# PCB_KIT_89S52_OBIT.net
KiCad netlist of a schematic drawn in Altium Designer
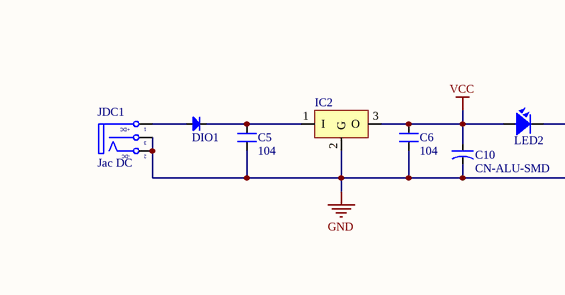
[diagram p0: PCB_KIT_89S52_OBIT.SchDoc, top left]
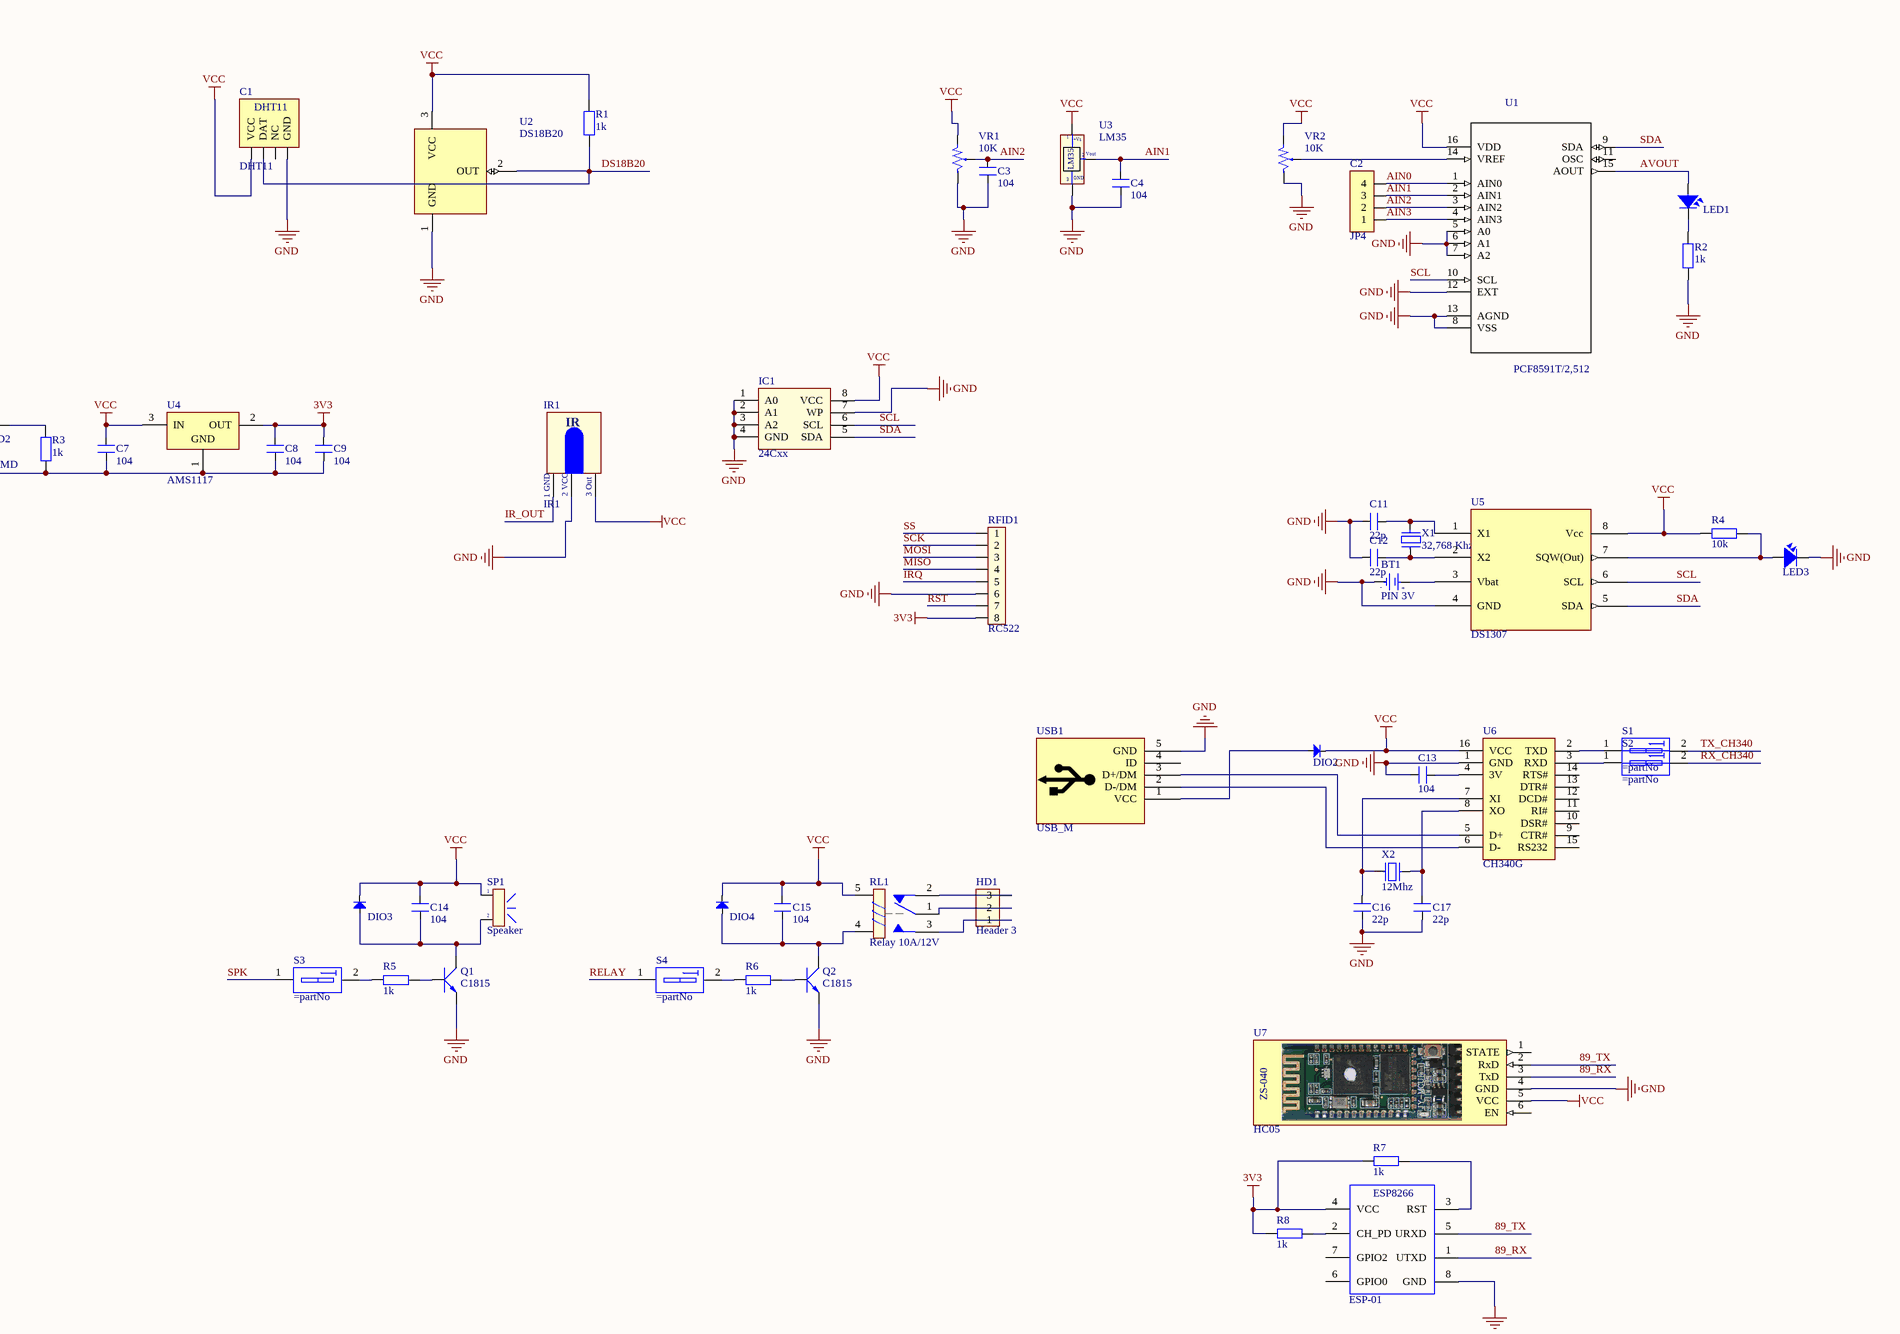
[diagram p1: PCB_KIT_89S52_OBIT.SchDoc, top right]
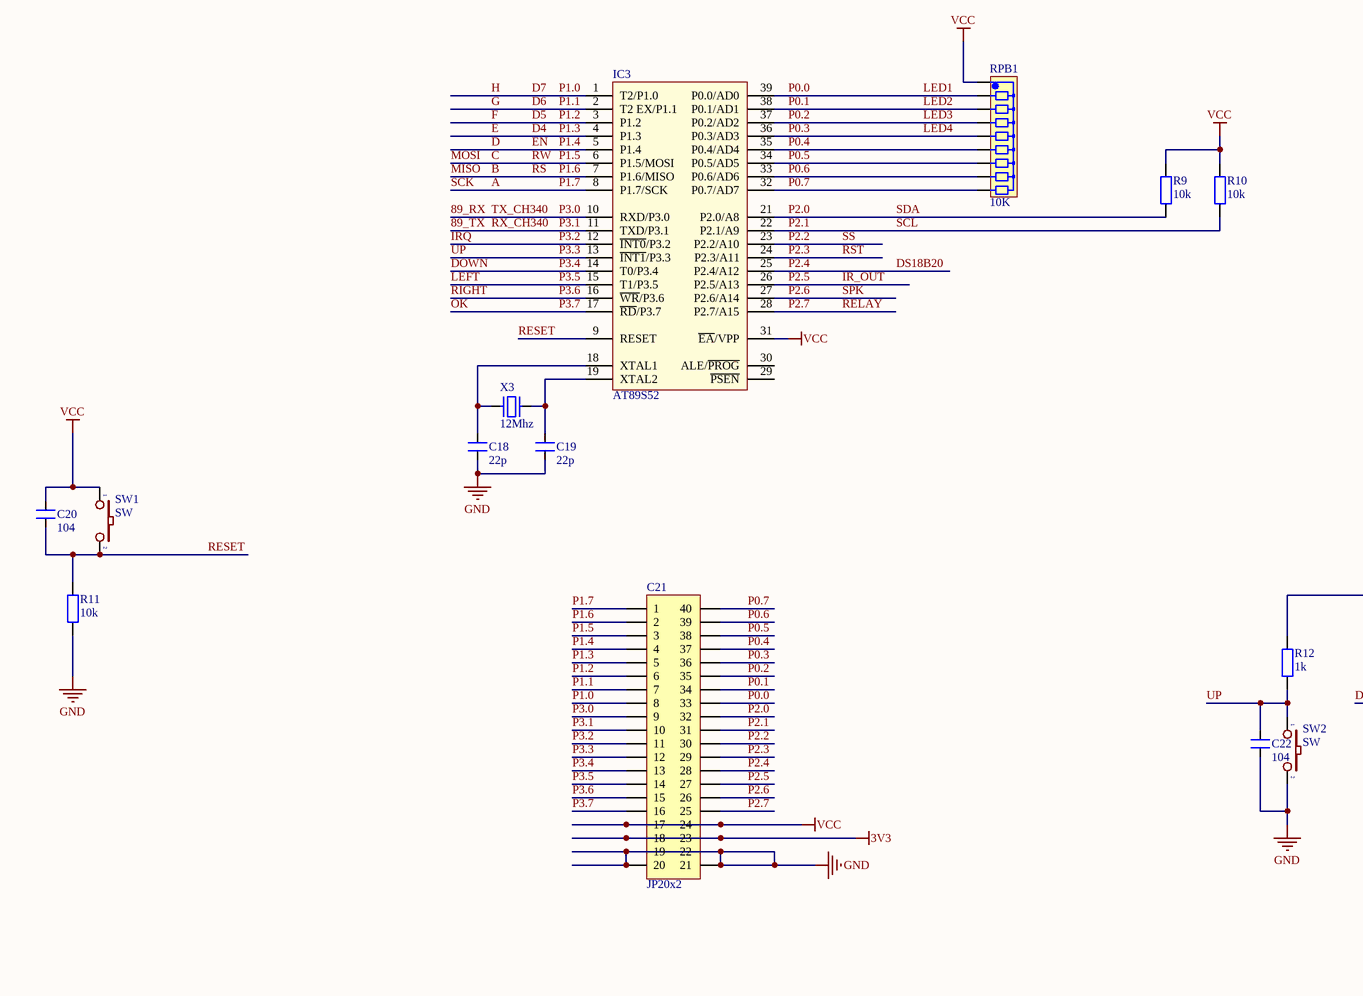
[diagram p2: PCB_KIT_89S52_OBIT.SchDoc, bottom left]
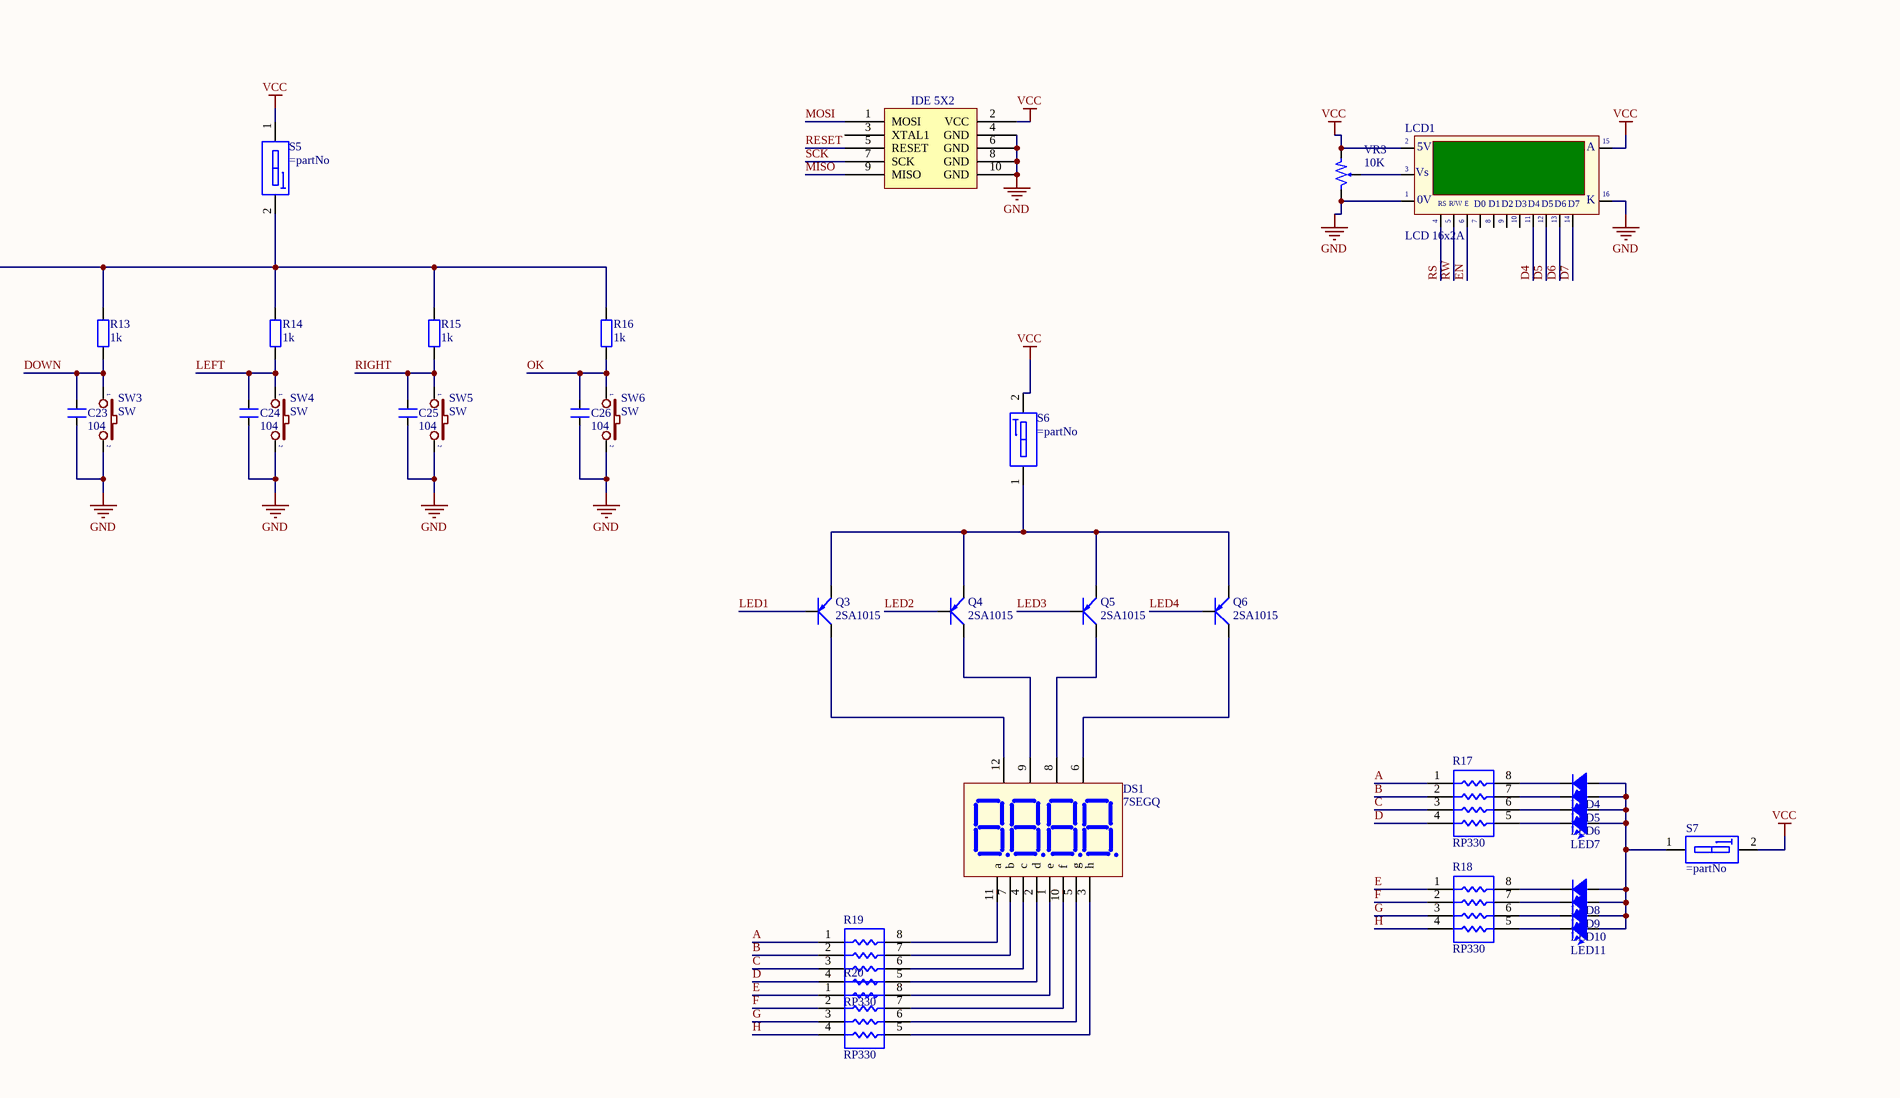
[diagram p3: PCB_KIT_89S52_OBIT.SchDoc, bottom right]

(export (version "E")
  (design (tool "Eeschema 10.0.6"))
  (components
    (comp (ref "BT1")
      (value "PIN 3V")
      (footprint "PIN CR1220-SMD")
      (description "Battery 3VDC")
      (libsource (lib "Tesla_Thinh") (part "PIN 3V"))
    )
    (comp (ref "C1")
      (value "DHT11")
      (footprint "DHT11")
      (fields
        (field (name "MANUFACTURER") "Würth Elektronik eiSos GmbH")
        (field (name "PARTNO") "613004143121")
        (field (name "CREATED BY") "Karrer Zheng")
      )
      (libsource (lib "Tesla_Thinh") (part "DHT11"))
    )
    (comp (ref "C2")
      (value "JP4")
      (footprint "JP4-C1T")
      (description "WR-PHD 2.54 mm Angled Socket Header")
      (fields
        (field (name "MANUFACTURER") "Würth Elektronik eiSos GmbH")
        (field (name "PARTNO") "613004143121")
        (field (name "CREATED BY") "Karrer Zheng")
      )
      (libsource (lib "Tesla_Thinh") (part "JP4"))
    )
    (comp (ref "C3")
      (value "104")
      (footprint "SM-0805")
      (description "Cap SMD")
      (libsource (lib "Tesla_Thinh") (part "CM"))
    )
    (comp (ref "C4")
      (value "104")
      (footprint "SM-0805")
      (description "Cap SMD")
      (libsource (lib "Tesla_Thinh") (part "CM"))
    )
    (comp (ref "C5")
      (value "104")
      (footprint "SM-0805")
      (description "Cap SMD")
      (libsource (lib "Tesla_Thinh") (part "CM"))
    )
    (comp (ref "C6")
      (value "104")
      (footprint "SM-0805")
      (description "Cap SMD")
      (libsource (lib "Tesla_Thinh") (part "CM"))
    )
    (comp (ref "C7")
      (value "104")
      (footprint "SM-0805")
      (description "Cap SMD")
      (libsource (lib "Tesla_Thinh") (part "CM"))
    )
    (comp (ref "C8")
      (value "104")
      (footprint "SM-0805")
      (description "Cap SMD")
      (libsource (lib "Tesla_Thinh") (part "CM"))
    )
    (comp (ref "C9")
      (value "104")
      (footprint "SM-0805")
      (description "Cap SMD")
      (libsource (lib "Tesla_Thinh") (part "CM"))
    )
    (comp (ref "C10")
      (value "CN-ALU-SMD")
      (footprint "CAP-ALU-SMD-5.5x5.5")
      (description "Polarized Capacitor (Axial)")
      (fields (field (name "PUBLISHER") "Altium Limited"))
      (libsource (lib "Tesla_Thinh") (part "CN-ALU-SMD"))
    )
    (comp (ref "C11")
      (value "22p")
      (footprint "SM-0805")
      (description "Cap SMD")
      (libsource (lib "Tesla_Thinh") (part "CM"))
    )
    (comp (ref "C12")
      (value "22p")
      (footprint "SM-0805")
      (description "Cap SMD")
      (libsource (lib "Tesla_Thinh") (part "CM"))
    )
    (comp (ref "C13")
      (value "104")
      (footprint "SM-0805")
      (description "Cap SMD")
      (libsource (lib "Tesla_Thinh") (part "CM"))
    )
    (comp (ref "C14")
      (value "104")
      (footprint "SM-0805")
      (description "Cap SMD")
      (libsource (lib "Tesla_Thinh") (part "CM"))
    )
    (comp (ref "C15")
      (value "104")
      (footprint "SM-0805")
      (description "Cap SMD")
      (libsource (lib "Tesla_Thinh") (part "CM"))
    )
    (comp (ref "C16")
      (value "22p")
      (footprint "SM-0805")
      (description "Cap SMD")
      (libsource (lib "Tesla_Thinh") (part "CM"))
    )
    (comp (ref "C17")
      (value "22p")
      (footprint "SM-0805")
      (description "Cap SMD")
      (libsource (lib "Tesla_Thinh") (part "CM"))
    )
    (comp (ref "C18")
      (value "22p")
      (footprint "SM-0805")
      (description "Cap SMD")
      (libsource (lib "Tesla_Thinh") (part "CM"))
    )
    (comp (ref "C19")
      (value "22p")
      (footprint "SM-0805")
      (description "Cap SMD")
      (libsource (lib "Tesla_Thinh") (part "CM"))
    )
    (comp (ref "C20")
      (value "104")
      (footprint "SM-0805")
      (description "Cap SMD")
      (libsource (lib "Tesla_Thinh") (part "CM"))
    )
    (comp (ref "C21")
      (value "JP20x2")
      (footprint "JP20-C2T")
      (description "WR-PHD 2.54 mm Dual Socket Header")
      (fields
        (field (name "MANUFACTURER") "Würth Elektronik eiSos GmbH")
        (field (name "PARTNO") "61304021821")
        (field (name "CREATED BY") "Karrer Zheng")
      )
      (libsource (lib "Tesla_Thinh") (part "JP20x2"))
    )
    (comp (ref "C22")
      (value "104")
      (footprint "SM-0805")
      (description "Cap SMD")
      (libsource (lib "Tesla_Thinh") (part "CM"))
    )
    (comp (ref "C23")
      (value "104")
      (footprint "SM-0805")
      (description "Cap SMD")
      (libsource (lib "Tesla_Thinh") (part "CM"))
    )
    (comp (ref "C24")
      (value "104")
      (footprint "SM-0805")
      (description "Cap SMD")
      (libsource (lib "Tesla_Thinh") (part "CM"))
    )
    (comp (ref "C25")
      (value "104")
      (footprint "SM-0805")
      (description "Cap SMD")
      (libsource (lib "Tesla_Thinh") (part "CM"))
    )
    (comp (ref "C26")
      (value "104")
      (footprint "SM-0805")
      (description "Cap SMD")
      (libsource (lib "Tesla_Thinh") (part "CM"))
    )
    (comp (ref "DIO1")
      (value "Diode SMD")
      (footprint "DIO-SMD-106")
      (description "Default Diode")
      (fields (field (name "PUBLISHER") "Altium Limited"))
      (libsource (lib "Obit_Library") (part "Diode SMD"))
    )
    (comp (ref "DIO2")
      (value "Diode SMD")
      (footprint "DIO-SMD-106")
      (description "Default Diode")
      (fields (field (name "PUBLISHER") "Altium Limited"))
      (libsource (lib "Obit_Library") (part "Diode SMD"))
    )
    (comp (ref "DIO3")
      (value "Diode SMD")
      (footprint "DIO-SMD-106")
      (description "Default Diode")
      (fields (field (name "PUBLISHER") "Altium Limited"))
      (libsource (lib "Obit_Library") (part "Diode SMD"))
    )
    (comp (ref "DIO4")
      (value "Diode SMD")
      (footprint "DIO-SMD-106")
      (description "Default Diode")
      (fields (field (name "PUBLISHER") "Altium Limited"))
      (libsource (lib "Obit_Library") (part "Diode SMD"))
    )
    (comp (ref "DS1")
      (value "7SEGQ")
      (footprint "LED7SEG-4-0.56")
      (description "Four 7 Seg Dipslay")
      (libsource (lib "Tesla_Thinh") (part "LED7SEG-4"))
    )
    (comp (ref "HD1")
      (value "Header 3")
      (footprint "HED3")
      (description "Header 3 (Green)")
      (libsource (lib "Obit_Library") (part "Hed3"))
    )
    (comp (ref "IC1")
      (value "24Cxx")
      (footprint "SO8")
      (description "Standard 2-Wire Bus Interface Serial EEPROM")
      (fields (field (name "COPYRIGHT BY") "VanDungEvn"))
      (libsource (lib "Obit_Library") (part "24Cxx"))
    )
    (comp (ref "IC2")
      (value "LM78xx")
      (footprint "TO252-123")
      (description "Positive Voltage Regulator")
      (fields (field (name "PUBLISHER") "Altium Limited"))
      (libsource (lib "Tesla_Thinh") (part "LM78xx"))
    )
    (comp (ref "IC3")
      (value "AT89S52")
      (footprint "DIP40_Socket")
      (description "AT89S52, 8k Byte Flash Memory , 40 Pin")
      (libsource (lib "Obit_Library") (part "AT89S52"))
    )
    (comp (ref "IDE_1")
      (value "IDE 5X2")
      (footprint "HDR2X5")
      (description "IDE 5X2 DUC-THANG")
      (libsource (lib "Lib_Chuan_03_08_2013") (part "ISP"))
    )
    (comp (ref "IR1")
      (value "IR1")
      (footprint "IR2")
      (description "Receiver Infraed IC")
      (libsource (lib "Tesla_Thinh") (part "IR1"))
    )
    (comp (ref "JDC1")
      (value "Jac DC")
      (footprint "DC0")
      (description "Jac DC input")
      (libsource (lib "Tesla_Thinh") (part "DCIN"))
    )
    (comp (ref "LCD1")
      (value "LCD 16x2A")
      (footprint "LCD16X2N")
      (description "LCD dipslay 16 char, 2 line")
      (libsource (lib "Tesla_Thinh") (part "LCD16x2A"))
    )
    (comp (ref "LED1")
      (value "LED")
      (footprint "LED-0805-Green")
      (libsource (lib "Tesla_Thinh") (part "LED SMD"))
    )
    (comp (ref "LED2")
      (value "LED")
      (footprint "LED-0805-Green")
      (libsource (lib "Tesla_Thinh") (part "LED SMD"))
    )
    (comp (ref "LED3")
      (value "LED")
      (footprint "LED-0805-Green")
      (libsource (lib "Tesla_Thinh") (part "LED SMD"))
    )
    (comp (ref "LED4")
      (value "LED")
      (footprint "LED-0805-Green")
      (libsource (lib "Tesla_Thinh") (part "LED SMD"))
    )
    (comp (ref "LED5")
      (value "LED")
      (footprint "LED-0805-Green")
      (libsource (lib "Tesla_Thinh") (part "LED SMD"))
    )
    (comp (ref "LED6")
      (value "LED")
      (footprint "LED-0805-Green")
      (libsource (lib "Tesla_Thinh") (part "LED SMD"))
    )
    (comp (ref "LED7")
      (value "LED")
      (footprint "LED-0805-Green")
      (libsource (lib "Tesla_Thinh") (part "LED SMD"))
    )
    (comp (ref "LED8")
      (value "LED")
      (footprint "LED-0805-Green")
      (libsource (lib "Tesla_Thinh") (part "LED SMD"))
    )
    (comp (ref "LED9")
      (value "LED")
      (footprint "LED-0805-Green")
      (libsource (lib "Tesla_Thinh") (part "LED SMD"))
    )
    (comp (ref "LED10")
      (value "LED")
      (footprint "LED-0805-Green")
      (libsource (lib "Tesla_Thinh") (part "LED SMD"))
    )
    (comp (ref "LED11")
      (value "LED")
      (footprint "LED-0805-Green")
      (libsource (lib "Tesla_Thinh") (part "LED SMD"))
    )
    (comp (ref "Q1")
      (value "C1815")
      (footprint "SOT23B")
      (description "NPN 600mW, ECB")
      (libsource (lib "Obit_Library") (part "C1815"))
    )
    (comp (ref "Q2")
      (value "C1815")
      (footprint "SOT23B")
      (description "NPN 600mW, ECB")
      (libsource (lib "Obit_Library") (part "C1815"))
    )
    (comp (ref "Q3")
      (value "2SA1015")
      (footprint "SOT23-321")
      (description "PNP 600mW, ECB")
      (libsource (lib "OBIT_TESLA") (part "2SA1015"))
    )
    (comp (ref "Q4")
      (value "2SA1015")
      (footprint "SOT23-321")
      (description "PNP 600mW, ECB")
      (libsource (lib "OBIT_TESLA") (part "2SA1015"))
    )
    (comp (ref "Q5")
      (value "2SA1015")
      (footprint "SOT23-321")
      (description "PNP 600mW, ECB")
      (libsource (lib "OBIT_TESLA") (part "2SA1015"))
    )
    (comp (ref "Q6")
      (value "2SA1015")
      (footprint "SOT23-321")
      (description "PNP 600mW, ECB")
      (libsource (lib "OBIT_TESLA") (part "2SA1015"))
    )
    (comp (ref "R1")
      (value "1k")
      (footprint "SM-RES-0805")
      (description "Resistor 1/4W")
      (libsource (lib "Tesla_Thinh") (part "R1/4W"))
    )
    (comp (ref "R2")
      (value "1k")
      (footprint "SM-RES-0805")
      (description "Resistor 1/4W")
      (libsource (lib "Tesla_Thinh") (part "R1/4W"))
    )
    (comp (ref "R3")
      (value "1k")
      (footprint "SM-RES-0805")
      (description "Resistor 1/4W")
      (libsource (lib "Tesla_Thinh") (part "R1/4W"))
    )
    (comp (ref "R4")
      (value "10k")
      (footprint "SM-RES-0805")
      (description "Resistor 1/4W")
      (libsource (lib "Tesla_Thinh") (part "R1/4W"))
    )
    (comp (ref "R5")
      (value "1k")
      (footprint "SM-RES-0805")
      (description "Resistor 1/4W")
      (libsource (lib "Tesla_Thinh") (part "R1/4W"))
    )
    (comp (ref "R6")
      (value "1k")
      (footprint "SM-RES-0805")
      (description "Resistor 1/4W")
      (libsource (lib "Tesla_Thinh") (part "R1/4W"))
    )
    (comp (ref "R7")
      (value "1k")
      (footprint "SM-RES-0805")
      (description "Resistor 1/4W")
      (libsource (lib "Tesla_Thinh") (part "R1/4W"))
    )
    (comp (ref "R8")
      (value "1k")
      (footprint "SM-RES-0805")
      (description "Resistor 1/4W")
      (libsource (lib "Tesla_Thinh") (part "R1/4W"))
    )
    (comp (ref "R9")
      (value "10k")
      (footprint "SM-RES-0805")
      (description "Resistor 1/4W")
      (libsource (lib "Tesla_Thinh") (part "R1/4W"))
    )
    (comp (ref "R10")
      (value "10k")
      (footprint "SM-RES-0805")
      (description "Resistor 1/4W")
      (libsource (lib "Tesla_Thinh") (part "R1/4W"))
    )
    (comp (ref "R11")
      (value "10k")
      (footprint "SM-RES-0805")
      (description "Resistor 1/4W")
      (libsource (lib "Tesla_Thinh") (part "R1/4W"))
    )
    (comp (ref "R12")
      (value "1k")
      (footprint "SM-RES-0805")
      (description "Resistor 1/4W")
      (libsource (lib "Tesla_Thinh") (part "R1/4W"))
    )
    (comp (ref "R13")
      (value "1k")
      (footprint "SM-RES-0805")
      (description "Resistor 1/4W")
      (libsource (lib "Tesla_Thinh") (part "R1/4W"))
    )
    (comp (ref "R14")
      (value "1k")
      (footprint "SM-RES-0805")
      (description "Resistor 1/4W")
      (libsource (lib "Tesla_Thinh") (part "R1/4W"))
    )
    (comp (ref "R15")
      (value "1k")
      (footprint "SM-RES-0805")
      (description "Resistor 1/4W")
      (libsource (lib "Tesla_Thinh") (part "R1/4W"))
    )
    (comp (ref "R16")
      (value "1k")
      (footprint "SM-RES-0805")
      (description "Resistor 1/4W")
      (libsource (lib "Tesla_Thinh") (part "R1/4W"))
    )
    (comp (ref "R17")
      (value "RP330")
      (footprint "RESCAXS50P160X320X70-8N")
      (libsource (lib "Obit_Library") (part "ResPack"))
    )
    (comp (ref "R18")
      (value "RP330")
      (footprint "RESCAXS50P160X320X70-8N")
      (libsource (lib "Obit_Library") (part "ResPack"))
    )
    (comp (ref "R19")
      (value "RP330")
      (footprint "RESCAXS50P160X320X70-8N")
      (libsource (lib "Obit_Library") (part "ResPack"))
    )
    (comp (ref "R20")
      (value "RP330")
      (footprint "RESCAXS50P160X320X70-8N")
      (libsource (lib "Obit_Library") (part "ResPack"))
    )
    (comp (ref "RFID1")
      (value "RC522")
      (footprint "JP8")
      (description "JP8 PIN")
      (libsource (lib "Obit_Library") (part "JP8"))
    )
    (comp (ref "RL1")
      (value "Relay 10A/12V")
      (footprint "RL_SPDT_10A")
      (description "Relay SPDT,10A - 12VDC 5 Pin")
      (libsource (lib "Obit_Library") (part "Relay 1"))
    )
    (comp (ref "RPB1")
      (value "10K")
      (footprint "RN8")
      (description "Resistor 8 (Thanh)")
      (libsource (lib "Tesla_Thinh") (part "RN8"))
    )
    (comp (ref "S1")
      (value "~")
      (footprint "SW-DIP1-1")
      (description "WS-DITV 2.54 mm small compact THT flat actuator with top tape")
      (fields
        (field (name "MANUFACTURER") "Wurth Elektronik")
        (field (name "PART NO.") "418127160901")
        (field (name "CREATED BY") "Baojun Chen")
      )
      (libsource (lib "Tesla_Thinh") (part "SWDIP1"))
    )
    (comp (ref "S2")
      (value "~")
      (footprint "SW-DIP1-1")
      (description "WS-DITV 2.54 mm small compact THT flat actuator with top tape")
      (fields
        (field (name "MANUFACTURER") "Wurth Elektronik")
        (field (name "PART NO.") "418127160901")
        (field (name "CREATED BY") "Baojun Chen")
      )
      (libsource (lib "Tesla_Thinh") (part "SWDIP1"))
    )
    (comp (ref "S3")
      (value "~")
      (footprint "SW-DIP1-1")
      (description "WS-DITV 2.54 mm small compact THT flat actuator with top tape")
      (fields
        (field (name "MANUFACTURER") "Wurth Elektronik")
        (field (name "PART NO.") "418127160901")
        (field (name "CREATED BY") "Baojun Chen")
      )
      (libsource (lib "Tesla_Thinh") (part "SWDIP1"))
    )
    (comp (ref "S4")
      (value "~")
      (footprint "SW-DIP1-1")
      (description "WS-DITV 2.54 mm small compact THT flat actuator with top tape")
      (fields
        (field (name "MANUFACTURER") "Wurth Elektronik")
        (field (name "PART NO.") "418127160901")
        (field (name "CREATED BY") "Baojun Chen")
      )
      (libsource (lib "Tesla_Thinh") (part "SWDIP1"))
    )
    (comp (ref "S5")
      (value "~")
      (footprint "SW-DIP1-1")
      (description "WS-DITV 2.54 mm small compact THT flat actuator with top tape")
      (fields
        (field (name "MANUFACTURER") "Wurth Elektronik")
        (field (name "PART NO.") "418127160901")
        (field (name "CREATED BY") "Baojun Chen")
      )
      (libsource (lib "") (part "SWDIP1_1"))
    )
    (comp (ref "S6")
      (value "~")
      (footprint "SW-DIP1-1")
      (description "WS-DITV 2.54 mm small compact THT flat actuator with top tape")
      (fields
        (field (name "MANUFACTURER") "Wurth Elektronik")
        (field (name "PART NO.") "418127160901")
        (field (name "CREATED BY") "Baojun Chen")
      )
      (libsource (lib "") (part "SWDIP1_2"))
    )
    (comp (ref "S7")
      (value "~")
      (footprint "SW-DIP1-1")
      (description "WS-DITV 2.54 mm small compact THT flat actuator with top tape")
      (fields
        (field (name "MANUFACTURER") "Wurth Elektronik")
        (field (name "PART NO.") "418127160901")
        (field (name "CREATED BY") "Baojun Chen")
      )
      (libsource (lib "Tesla_Thinh") (part "SWDIP1"))
    )
    (comp (ref "SP1")
      (value "Speaker")
      (footprint "SPK")
      (description "Speaker Chip")
      (libsource (lib "Obit_Library") (part "SPK"))
    )
    (comp (ref "SW1")
      (value "SW")
      (footprint "SW1-SMD")
      (description "Switch button 2 pin")
      (libsource (lib "Tesla_Thinh") (part "SW2"))
    )
    (comp (ref "SW2")
      (value "SW")
      (footprint "SW1-SMD")
      (description "Switch button 2 pin")
      (libsource (lib "Tesla_Thinh") (part "SW2"))
    )
    (comp (ref "SW3")
      (value "SW")
      (footprint "SW1-SMD")
      (description "Switch button 2 pin")
      (libsource (lib "Tesla_Thinh") (part "SW2"))
    )
    (comp (ref "SW4")
      (value "SW")
      (footprint "SW1-SMD")
      (description "Switch button 2 pin")
      (libsource (lib "Tesla_Thinh") (part "SW2"))
    )
    (comp (ref "SW5")
      (value "SW")
      (footprint "SW1-SMD")
      (description "Switch button 2 pin")
      (libsource (lib "Tesla_Thinh") (part "SW2"))
    )
    (comp (ref "SW6")
      (value "SW")
      (footprint "SW1-SMD")
      (description "Switch button 2 pin")
      (libsource (lib "Tesla_Thinh") (part "SW2"))
    )
    (comp (ref "U1")
      (value "PCF8591T/2,512")
      (footprint "SOIC127P1032X265-16N")
      (description "PCF8591 Series 2.5 V - 6 V Bá»™ chuyá»ƒn Ä‘á»•i A / D 8-bit vÃ  D / A - SOIC - 16")
      (fields (field (name "MF") "NXP Semiconductors"))
      (libsource (lib "PCF8591T_2_512") (part "PCF8591T/2,512"))
    )
    (comp (ref "U2")
      (value "DS18B20")
      (footprint "TO-92A")
      (description "1-Wire Digital Thermometer")
      (fields (field (name "CREATOR") "Cao Van Huong"))
      (libsource (lib "Obit_Library") (part "DS18B20"))
    )
    (comp (ref "U3")
      (value "LM35")
      (footprint "TO92-123")
      (description "Teminal")
      (libsource (lib "Tesla_Thinh") (part "LM35"))
    )
    (comp (ref "U4") (value "AMS1117") (footprint "SOT 223") (libsource (lib "Obit_Library") (part "AMS117")))
    (comp (ref "U5")
      (value "DS1307")
      (footprint "SOP 8")
      (description "64 X 8 Serial Real-Time Clock")
      (libsource (lib "Obit_Library") (part "DS1307"))
    )
    (comp (ref "U6")
      (value "CH340G")
      (footprint "SO16")
      (description "High and Low Side Driver")
      (fields (field (name "PUBLISHER") "Altium Limited"))
      (libsource (lib "Obit_Library") (part "CH340G"))
    )
    (comp (ref "U7")
      (value "HC05")
      (footprint "JP6-C1T")
      (libsource (lib "Tesla_Thinh") (part "Module ZS-040 (HC05)"))
    )
    (comp (ref "U8")
      (value "ESP-01")
      (footprint "ESP8266")
      (description "ESP-12 Wi-Fi Module")
      (libsource (lib "Tesla_Thinh") (part "ESP8266-01"))
    )
    (comp (ref "USB1") (value "USB_M") (footprint "USB-M1") (libsource (lib "OBIT_TESLA") (part "USB_M")))
    (comp (ref "VR1")
      (value "10K")
      (footprint "VR1")
      (description "Var Resistor")
      (libsource (lib "Tesla_Thinh") (part "VR1"))
    )
    (comp (ref "VR2")
      (value "10K")
      (footprint "VR1")
      (description "Var Resistor")
      (libsource (lib "Tesla_Thinh") (part "VR1"))
    )
    (comp (ref "VR3")
      (value "10K")
      (footprint "VR")
      (description "Var Resistor")
      (libsource (lib "Tesla_Thinh") (part "VR1"))
    )
    (comp (ref "X1")
      (value "32,768 Khz")
      (footprint "XT32k")
      (description "Crystal 32,768kHz for timer real")
      (libsource (lib "Tesla_Thinh") (part "XT32k"))
    )
    (comp (ref "X2")
      (value "12Mhz")
      (footprint "XT2")
      (description "Crystal, 32.768 KHz, -40 to 85 degC, 3.2 x 1.5 x 0.9 mm SMD")
      (libsource (lib "Tesla_Thinh") (part "XT2"))
    )
    (comp (ref "X3")
      (value "12Mhz")
      (footprint "XT2")
      (description "Crystal, 32.768 KHz, -40 to 85 degC, 3.2 x 1.5 x 0.9 mm SMD")
      (libsource (lib "Tesla_Thinh") (part "XT2"))
    )
  )
  (nets
    (net (code "1") (name "/89_RX") (class "Default")
      (node (ref "C21") (pin "9") (pinfunction "9_9") (pintype "passive"))
      (node (ref "IC3") (pin "10") (pinfunction "RXD/P3.0_10") (pintype "passive"))
      (node (ref "S1") (pin "2") (pinfunction "2_2") (pintype "passive"))
      (node (ref "U7") (pin "3") (pinfunction "TxD_3") (pintype "power_in"))
      (node (ref "U8") (pin "1") (pinfunction "UTXD_1") (pintype "passive"))
    )
    (net (code "2") (name "/89_TX") (class "Default")
      (node (ref "C21") (pin "10") (pinfunction "10_10") (pintype "passive"))
      (node (ref "IC3") (pin "11") (pinfunction "TXD/P3.1_11") (pintype "passive"))
      (node (ref "S2") (pin "2") (pinfunction "2_2") (pintype "passive"))
      (node (ref "U7") (pin "2") (pinfunction "RxD_2") (pintype "input"))
      (node (ref "U8") (pin "5") (pinfunction "URXD_5") (pintype "passive"))
    )
    (net (code "3") (name "/A") (class "Default")
      (node (ref "C21") (pin "1") (pinfunction "1_1") (pintype "passive"))
      (node (ref "IC3") (pin "8") (pinfunction "P1.7/SCK_8") (pintype "passive"))
      (node (ref "IDE_1") (pin "7") (pinfunction "SCK_7") (pintype "passive"))
      (node (ref "R17") (pin "1") (pinfunction "1_1") (pintype "passive"))
      (node (ref "R19") (pin "1") (pinfunction "1_1") (pintype "passive"))
      (node (ref "RFID1") (pin "2") (pinfunction "2_2") (pintype "passive"))
    )
    (net (code "4") (name "/AIN0") (class "Default")
      (node (ref "C2") (pin "4") (pinfunction "4_4") (pintype "passive"))
      (node (ref "U1") (pin "1") (pinfunction "AIN0_1") (pintype "input"))
    )
    (net (code "5") (name "/AIN1") (class "Default")
      (node (ref "C2") (pin "3") (pinfunction "3_3") (pintype "passive"))
      (node (ref "C4") (pin "1") (pinfunction "1_1") (pintype "passive"))
      (node (ref "U1") (pin "2") (pinfunction "AIN1_2") (pintype "input"))
      (node (ref "U3") (pin "2") (pinfunction "Vout_2") (pintype "passive"))
    )
    (net (code "6") (name "/AIN2") (class "Default")
      (node (ref "C2") (pin "2") (pinfunction "2_2") (pintype "passive"))
      (node (ref "C3") (pin "1") (pinfunction "1_1") (pintype "passive"))
      (node (ref "U1") (pin "3") (pinfunction "AIN2_3") (pintype "input"))
      (node (ref "VR1") (pin "2") (pinfunction "2_2") (pintype "passive"))
    )
    (net (code "7") (name "/AIN3") (class "Default")
      (node (ref "C2") (pin "1") (pinfunction "1_1") (pintype "passive"))
      (node (ref "U1") (pin "4") (pinfunction "AIN3_4") (pintype "input"))
    )
    (net (code "8") (name "/AVOUT") (class "Default")
      (node (ref "LED1") (pin "1") (pinfunction "1_1") (pintype "passive"))
      (node (ref "U1") (pin "15") (pinfunction "AOUT_15") (pintype "output"))
    )
    (net (code "9") (name "/B") (class "Default")
      (node (ref "C21") (pin "2") (pinfunction "2_2") (pintype "passive"))
      (node (ref "IC3") (pin "7") (pinfunction "P1.6/MISO_7") (pintype "passive"))
      (node (ref "IDE_1") (pin "9") (pinfunction "MISO_9") (pintype "passive"))
      (node (ref "LCD1") (pin "4") (pinfunction "RS_4") (pintype "passive"))
      (node (ref "R17") (pin "2") (pinfunction "2_2") (pintype "passive"))
      (node (ref "R19") (pin "2") (pinfunction "2_2") (pintype "passive"))
      (node (ref "RFID1") (pin "4") (pinfunction "4_4") (pintype "passive"))
    )
    (net (code "10") (name "/C") (class "Default")
      (node (ref "C21") (pin "3") (pinfunction "3_3") (pintype "passive"))
      (node (ref "IC3") (pin "6") (pinfunction "P1.5/MOSI_6") (pintype "passive"))
      (node (ref "IDE_1") (pin "1") (pinfunction "MOSI_1") (pintype "passive"))
      (node (ref "LCD1") (pin "5") (pinfunction "R/~{W}_5") (pintype "passive"))
      (node (ref "R17") (pin "3") (pinfunction "3_3") (pintype "passive"))
      (node (ref "R19") (pin "3") (pinfunction "3_3") (pintype "passive"))
      (node (ref "RFID1") (pin "3") (pinfunction "3_3") (pintype "passive"))
    )
    (net (code "11") (name "/D") (class "Default")
      (node (ref "C21") (pin "4") (pinfunction "4_4") (pintype "passive"))
      (node (ref "IC3") (pin "5") (pinfunction "P1.4_5") (pintype "passive"))
      (node (ref "LCD1") (pin "6") (pinfunction "~{EN}_6") (pintype "passive"))
      (node (ref "R17") (pin "4") (pinfunction "4_4") (pintype "passive"))
      (node (ref "R19") (pin "4") (pinfunction "4_4") (pintype "passive"))
    )
    (net (code "12") (name "/D4") (class "Default")
      (node (ref "C21") (pin "5") (pinfunction "5_5") (pintype "passive"))
      (node (ref "IC3") (pin "4") (pinfunction "P1.3_4") (pintype "passive"))
      (node (ref "LCD1") (pin "11") (pinfunction "D4_11") (pintype "passive"))
      (node (ref "R18") (pin "1") (pinfunction "1_1") (pintype "passive"))
      (node (ref "R20") (pin "1") (pinfunction "1_1") (pintype "passive"))
    )
    (net (code "13") (name "/D5") (class "Default")
      (node (ref "C21") (pin "6") (pinfunction "6_6") (pintype "passive"))
      (node (ref "IC3") (pin "3") (pinfunction "P1.2_3") (pintype "passive"))
      (node (ref "LCD1") (pin "12") (pinfunction "D5_12") (pintype "passive"))
      (node (ref "R18") (pin "2") (pinfunction "2_2") (pintype "passive"))
      (node (ref "R20") (pin "2") (pinfunction "2_2") (pintype "passive"))
    )
    (net (code "14") (name "/D6") (class "Default")
      (node (ref "C21") (pin "7") (pinfunction "7_7") (pintype "passive"))
      (node (ref "IC3") (pin "2") (pinfunction "T2_EX/P1.1_2") (pintype "passive"))
      (node (ref "LCD1") (pin "13") (pinfunction "D6_13") (pintype "passive"))
      (node (ref "R18") (pin "3") (pinfunction "3_3") (pintype "passive"))
      (node (ref "R20") (pin "3") (pinfunction "3_3") (pintype "passive"))
    )
    (net (code "15") (name "/D7") (class "Default")
      (node (ref "C21") (pin "8") (pinfunction "8_8") (pintype "passive"))
      (node (ref "IC3") (pin "1") (pinfunction "T2/P1.0_1") (pintype "passive"))
      (node (ref "LCD1") (pin "14") (pinfunction "D7_14") (pintype "passive"))
      (node (ref "R18") (pin "4") (pinfunction "4_4") (pintype "passive"))
      (node (ref "R20") (pin "4") (pinfunction "4_4") (pintype "passive"))
    )
    (net (code "16") (name "/DOWN") (class "Default")
      (node (ref "C21") (pin "13") (pinfunction "13_13") (pintype "passive"))
      (node (ref "C23") (pin "1") (pinfunction "1_1") (pintype "passive"))
      (node (ref "IC3") (pin "14") (pinfunction "T0/P3.4_14") (pintype "passive"))
      (node (ref "R13") (pin "2") (pinfunction "2_2") (pintype "passive"))
      (node (ref "SW3") (pin "1") (pinfunction "1_1") (pintype "passive"))
    )
    (net (code "17") (name "/DS18B20") (class "Default")
      (node (ref "C1") (pin "2") (pinfunction "DAT_2") (pintype "passive"))
      (node (ref "C21") (pin "28") (pinfunction "28_28") (pintype "passive"))
      (node (ref "IC3") (pin "25") (pinfunction "P2.4/A12_25") (pintype "passive"))
      (node (ref "R1") (pin "2") (pinfunction "2_2") (pintype "passive"))
      (node (ref "U2") (pin "2") (pinfunction "OUT_2") (pintype "bidirectional"))
    )
    (net (code "18") (name "/IRQ") (class "Default")
      (node (ref "C21") (pin "11") (pinfunction "11_11") (pintype "passive"))
      (node (ref "IC3") (pin "12") (pinfunction "~{INT0}/P3.2_12") (pintype "passive"))
      (node (ref "RFID1") (pin "5") (pinfunction "5_5") (pintype "passive"))
    )
    (net (code "19") (name "/IR_OUT") (class "Default")
      (node (ref "C21") (pin "27") (pinfunction "27_27") (pintype "passive"))
      (node (ref "IC3") (pin "26") (pinfunction "P2.5/A13_26") (pintype "passive"))
      (node (ref "IR1") (pin "1") (pinfunction "Out_1") (pintype "passive"))
    )
    (net (code "20") (name "/LED1") (class "Default")
      (node (ref "C21") (pin "33") (pinfunction "33_33") (pintype "passive"))
      (node (ref "IC3") (pin "39") (pinfunction "P0.0/AD0_39") (pintype "passive"))
      (node (ref "Q3") (pin "3") (pinfunction "B_3") (pintype "passive"))
      (node (ref "RPB1") (pin "2") (pinfunction "2_2") (pintype "passive"))
    )
    (net (code "21") (name "/LED2") (class "Default")
      (node (ref "C21") (pin "34") (pinfunction "34_34") (pintype "passive"))
      (node (ref "IC3") (pin "38") (pinfunction "P0.1/AD1_38") (pintype "passive"))
      (node (ref "Q4") (pin "3") (pinfunction "B_3") (pintype "passive"))
      (node (ref "RPB1") (pin "3") (pinfunction "3_3") (pintype "passive"))
    )
    (net (code "22") (name "/LED3") (class "Default")
      (node (ref "C21") (pin "35") (pinfunction "35_35") (pintype "passive"))
      (node (ref "IC3") (pin "37") (pinfunction "P0.2/AD2_37") (pintype "passive"))
      (node (ref "Q5") (pin "3") (pinfunction "B_3") (pintype "passive"))
      (node (ref "RPB1") (pin "4") (pinfunction "4_4") (pintype "passive"))
    )
    (net (code "23") (name "/LED4") (class "Default")
      (node (ref "C21") (pin "36") (pinfunction "36_36") (pintype "passive"))
      (node (ref "IC3") (pin "36") (pinfunction "P0.3/AD3_36") (pintype "passive"))
      (node (ref "Q6") (pin "3") (pinfunction "B_3") (pintype "passive"))
      (node (ref "RPB1") (pin "5") (pinfunction "5_5") (pintype "passive"))
    )
    (net (code "24") (name "/LEFT") (class "Default")
      (node (ref "C21") (pin "14") (pinfunction "14_14") (pintype "passive"))
      (node (ref "C24") (pin "1") (pinfunction "1_1") (pintype "passive"))
      (node (ref "IC3") (pin "15") (pinfunction "T1/P3.5_15") (pintype "passive"))
      (node (ref "R14") (pin "2") (pinfunction "2_2") (pintype "passive"))
      (node (ref "SW4") (pin "1") (pinfunction "1_1") (pintype "passive"))
    )
    (net (code "25") (name "/OK") (class "Default")
      (node (ref "C21") (pin "16") (pinfunction "16_16") (pintype "passive"))
      (node (ref "C26") (pin "1") (pinfunction "1_1") (pintype "passive"))
      (node (ref "IC3") (pin "17") (pinfunction "~{RD}/P3.7_17") (pintype "passive"))
      (node (ref "R16") (pin "2") (pinfunction "2_2") (pintype "passive"))
      (node (ref "SW6") (pin "1") (pinfunction "1_1") (pintype "passive"))
    )
    (net (code "26") (name "/P0.4") (class "Default")
      (node (ref "C21") (pin "37") (pinfunction "37_37") (pintype "passive"))
      (node (ref "IC3") (pin "35") (pinfunction "P0.4/AD4_35") (pintype "passive"))
      (node (ref "RPB1") (pin "6") (pinfunction "6_6") (pintype "passive"))
    )
    (net (code "27") (name "/P0.5") (class "Default")
      (node (ref "C21") (pin "38") (pinfunction "38_38") (pintype "passive"))
      (node (ref "IC3") (pin "34") (pinfunction "P0.5/AD5_34") (pintype "passive"))
      (node (ref "RPB1") (pin "7") (pinfunction "7_7") (pintype "passive"))
    )
    (net (code "28") (name "/P0.6") (class "Default")
      (node (ref "C21") (pin "39") (pinfunction "39_39") (pintype "passive"))
      (node (ref "IC3") (pin "33") (pinfunction "P0.6/AD6_33") (pintype "passive"))
      (node (ref "RPB1") (pin "8") (pinfunction "8_8") (pintype "passive"))
    )
    (net (code "29") (name "/P0.7") (class "Default")
      (node (ref "C21") (pin "40") (pinfunction "40_40") (pintype "passive"))
      (node (ref "IC3") (pin "32") (pinfunction "P0.7/AD7_32") (pintype "passive"))
      (node (ref "RPB1") (pin "9") (pinfunction "9_9") (pintype "passive"))
    )
    (net (code "30") (name "/P2.0") (class "Default")
      (node (ref "C21") (pin "32") (pinfunction "32_32") (pintype "passive"))
      (node (ref "IC1") (pin "5") (pinfunction "SDA_5") (pintype "passive"))
      (node (ref "IC3") (pin "21") (pinfunction "P2.0/A8_21") (pintype "passive"))
      (node (ref "R9") (pin "2") (pinfunction "2_2") (pintype "passive"))
      (node (ref "U1") (pin "9") (pinfunction "SDA_9") (pintype "bidirectional"))
      (node (ref "U5") (pin "5") (pinfunction "SDA_5") (pintype "output"))
    )
    (net (code "31") (name "/P2.1") (class "Default")
      (node (ref "C21") (pin "31") (pinfunction "31_31") (pintype "passive"))
      (node (ref "IC1") (pin "6") (pinfunction "SCL_6") (pintype "passive"))
      (node (ref "IC3") (pin "22") (pinfunction "P2.1/A9_22") (pintype "passive"))
      (node (ref "R10") (pin "2") (pinfunction "2_2") (pintype "passive"))
      (node (ref "U1") (pin "10") (pinfunction "SCL_10") (pintype "input"))
      (node (ref "U5") (pin "6") (pinfunction "SCL_6") (pintype "output"))
    )
    (net (code "32") (name "/P2.2") (class "Default")
      (node (ref "C21") (pin "30") (pinfunction "30_30") (pintype "passive"))
      (node (ref "IC3") (pin "23") (pinfunction "P2.2/A10_23") (pintype "passive"))
      (node (ref "RFID1") (pin "1") (pinfunction "1_1") (pintype "passive"))
    )
    (net (code "33") (name "/P2.3") (class "Default")
      (node (ref "C21") (pin "29") (pinfunction "29_29") (pintype "passive"))
      (node (ref "IC3") (pin "24") (pinfunction "P2.3/A11_24") (pintype "passive"))
      (node (ref "RFID1") (pin "7") (pinfunction "7_7") (pintype "passive"))
    )
    (net (code "34") (name "/P2.6") (class "Default")
      (node (ref "C21") (pin "26") (pinfunction "26_26") (pintype "passive"))
      (node (ref "IC3") (pin "27") (pinfunction "P2.6/A14_27") (pintype "passive"))
      (node (ref "S3") (pin "1") (pinfunction "1_1") (pintype "passive"))
    )
    (net (code "35") (name "/P2.7") (class "Default")
      (node (ref "C21") (pin "25") (pinfunction "25_25") (pintype "passive"))
      (node (ref "IC3") (pin "28") (pinfunction "P2.7/A15_28") (pintype "passive"))
      (node (ref "S4") (pin "1") (pinfunction "1_1") (pintype "passive"))
    )
    (net (code "36") (name "/P3.3") (class "Default")
      (node (ref "C21") (pin "12") (pinfunction "12_12") (pintype "passive"))
      (node (ref "C22") (pin "1") (pinfunction "1_1") (pintype "passive"))
      (node (ref "IC3") (pin "13") (pinfunction "~{INT1}/P3.3_13") (pintype "passive"))
      (node (ref "R12") (pin "2") (pinfunction "2_2") (pintype "passive"))
      (node (ref "SW2") (pin "1") (pinfunction "1_1") (pintype "passive"))
    )
    (net (code "37") (name "/P3.6") (class "Default")
      (node (ref "C21") (pin "15") (pinfunction "15_15") (pintype "passive"))
      (node (ref "C25") (pin "1") (pinfunction "1_1") (pintype "passive"))
      (node (ref "IC3") (pin "16") (pinfunction "~{WR}/P3.6_16") (pintype "passive"))
      (node (ref "R15") (pin "2") (pinfunction "2_2") (pintype "passive"))
      (node (ref "SW5") (pin "1") (pinfunction "1_1") (pintype "passive"))
    )
    (net (code "38") (name "/RESET") (class "Default")
      (node (ref "C20") (pin "2") (pinfunction "2_2") (pintype "passive"))
      (node (ref "IC3") (pin "9") (pinfunction "RESET_9") (pintype "passive"))
      (node (ref "IDE_1") (pin "5") (pinfunction "RESET_5") (pintype "passive"))
      (node (ref "R11") (pin "1") (pinfunction "1_1") (pintype "passive"))
      (node (ref "SW1") (pin "2") (pinfunction "2_2") (pintype "passive"))
    )
    (net (code "39") (name "3V3") (class "Default")
      (node (ref "C21") (pin "18") (pinfunction "18_18") (pintype "passive"))
      (node (ref "C21") (pin "23") (pinfunction "23_23") (pintype "passive"))
      (node (ref "C8") (pin "1") (pinfunction "1_1") (pintype "passive"))
      (node (ref "C9") (pin "1") (pinfunction "1_1") (pintype "passive"))
      (node (ref "R7") (pin "1") (pinfunction "1_1") (pintype "passive"))
      (node (ref "R8") (pin "1") (pinfunction "1_1") (pintype "passive"))
      (node (ref "RFID1") (pin "8") (pinfunction "8_8") (pintype "passive"))
      (node (ref "U4") (pin "2") (pinfunction "OUT_2") (pintype "power_in"))
      (node (ref "U8") (pin "4") (pinfunction "VCC_4") (pintype "passive"))
    )
    (net (code "40") (name "GND") (class "Default")
      (node (ref "BT1") (pin "2") (pinfunction "GND_2") (pintype "passive"))
      (node (ref "C1") (pin "4") (pinfunction "GND_4") (pintype "passive"))
      (node (ref "C10") (pin "2") (pinfunction "2_2") (pintype "passive"))
      (node (ref "C11") (pin "2") (pinfunction "2_2") (pintype "passive"))
      (node (ref "C12") (pin "2") (pinfunction "2_2") (pintype "passive"))
      (node (ref "C13") (pin "1") (pinfunction "1_1") (pintype "passive"))
      (node (ref "C16") (pin "2") (pinfunction "2_2") (pintype "passive"))
      (node (ref "C17") (pin "2") (pinfunction "2_2") (pintype "passive"))
      (node (ref "C18") (pin "2") (pinfunction "2_2") (pintype "passive"))
      (node (ref "C19") (pin "2") (pinfunction "2_2") (pintype "passive"))
      (node (ref "C21") (pin "19") (pinfunction "19_19") (pintype "passive"))
      (node (ref "C21") (pin "20") (pinfunction "20_20") (pintype "passive"))
      (node (ref "C21") (pin "21") (pinfunction "21_21") (pintype "passive"))
      (node (ref "C21") (pin "22") (pinfunction "22_22") (pintype "passive"))
      (node (ref "C22") (pin "2") (pinfunction "2_2") (pintype "passive"))
      (node (ref "C23") (pin "2") (pinfunction "2_2") (pintype "passive"))
      (node (ref "C24") (pin "2") (pinfunction "2_2") (pintype "passive"))
      (node (ref "C25") (pin "2") (pinfunction "2_2") (pintype "passive"))
      (node (ref "C26") (pin "2") (pinfunction "2_2") (pintype "passive"))
      (node (ref "C3") (pin "2") (pinfunction "2_2") (pintype "passive"))
      (node (ref "C4") (pin "2") (pinfunction "2_2") (pintype "passive"))
      (node (ref "C5") (pin "2") (pinfunction "2_2") (pintype "passive"))
      (node (ref "C6") (pin "2") (pinfunction "2_2") (pintype "passive"))
      (node (ref "C7") (pin "2") (pinfunction "2_2") (pintype "passive"))
      (node (ref "C8") (pin "2") (pinfunction "2_2") (pintype "passive"))
      (node (ref "C9") (pin "2") (pinfunction "2_2") (pintype "passive"))
      (node (ref "IC1") (pin "1") (pinfunction "A0_1") (pintype "passive"))
      (node (ref "IC1") (pin "2") (pinfunction "A1_2") (pintype "passive"))
      (node (ref "IC1") (pin "3") (pinfunction "A2_3") (pintype "passive"))
      (node (ref "IC1") (pin "4") (pinfunction "GND_4") (pintype "power_in"))
      (node (ref "IC1") (pin "7") (pinfunction "WP_7") (pintype "passive"))
      (node (ref "IC2") (pin "2") (pinfunction "G_2") (pintype "power_in"))
      (node (ref "IC3") (pin "20") (pinfunction "GND_20") (pintype "power_in"))
      (node (ref "IDE_1") (pin "10") (pinfunction "GND_10") (pintype "passive"))
      (node (ref "IDE_1") (pin "4") (pinfunction "GND_4") (pintype "passive"))
      (node (ref "IDE_1") (pin "6") (pinfunction "GND_6") (pintype "passive"))
      (node (ref "IDE_1") (pin "8") (pinfunction "GND_8") (pintype "passive"))
      (node (ref "IR1") (pin "2") (pinfunction "GND_2") (pintype "passive"))
      (node (ref "JDC1") (pin "2") (pinfunction "TN_2") (pintype "passive"))
      (node (ref "JDC1") (pin "3") (pinfunction "S_3") (pintype "power_in"))
      (node (ref "LCD1") (pin "1") (pinfunction "GND_1") (pintype "passive"))
      (node (ref "LCD1") (pin "16") (pinfunction "K_16") (pintype "passive"))
      (node (ref "LED3") (pin "2") (pinfunction "2_2") (pintype "passive"))
      (node (ref "Q1") (pin "1") (pinfunction "E_1") (pintype "passive"))
      (node (ref "Q2") (pin "1") (pinfunction "E_1") (pintype "passive"))
      (node (ref "R11") (pin "2") (pinfunction "2_2") (pintype "passive"))
      (node (ref "R2") (pin "2") (pinfunction "2_2") (pintype "passive"))
      (node (ref "R3") (pin "2") (pinfunction "2_2") (pintype "passive"))
      (node (ref "RFID1") (pin "6") (pinfunction "6_6") (pintype "passive"))
      (node (ref "SW2") (pin "2") (pinfunction "2_2") (pintype "passive"))
      (node (ref "SW3") (pin "2") (pinfunction "2_2") (pintype "passive"))
      (node (ref "SW4") (pin "2") (pinfunction "2_2") (pintype "passive"))
      (node (ref "SW5") (pin "2") (pinfunction "2_2") (pintype "passive"))
      (node (ref "SW6") (pin "2") (pinfunction "2_2") (pintype "passive"))
      (node (ref "U1") (pin "12") (pinfunction "EXT_12") (pintype "passive"))
      (node (ref "U1") (pin "13") (pinfunction "AGND_13") (pintype "passive"))
      (node (ref "U1") (pin "5") (pinfunction "A0_5") (pintype "input"))
      (node (ref "U1") (pin "6") (pinfunction "A1_6") (pintype "input"))
      (node (ref "U1") (pin "7") (pinfunction "A2_7") (pintype "input"))
      (node (ref "U1") (pin "8") (pinfunction "VSS_8") (pintype "power_in"))
      (node (ref "U2") (pin "1") (pinfunction "GND_1") (pintype "passive"))
      (node (ref "U3") (pin "3") (pinfunction "-_3") (pintype "passive"))
      (node (ref "U4") (pin "1") (pinfunction "GND_1") (pintype "power_in"))
      (node (ref "U5") (pin "4") (pinfunction "GND_4") (pintype "power_in"))
      (node (ref "U6") (pin "1") (pinfunction "GND_1") (pintype "passive"))
      (node (ref "U7") (pin "4") (pinfunction "GND_4") (pintype "power_in"))
      (node (ref "U8") (pin "8") (pinfunction "GND_8") (pintype "passive"))
      (node (ref "USB1") (pin "5") (pinfunction "GND_5") (pintype "passive"))
      (node (ref "VR1") (pin "3") (pinfunction "3_3") (pintype "passive"))
      (node (ref "VR2") (pin "3") (pinfunction "3_3") (pintype "passive"))
      (node (ref "VR3") (pin "3") (pinfunction "3_3") (pintype "passive"))
    )
    (net (code "41") (name "Net-(BT1-+3V)") (class "Default")
      (node (ref "BT1") (pin "1") (pinfunction "+3V_1") (pintype "passive"))
      (node (ref "U5") (pin "3") (pinfunction "Vbat_3") (pintype "passive"))
    )
    (net (code "42") (name "Net-(DIO1-A)") (class "Default")
      (node (ref "DIO1") (pin "1") (pinfunction "A_1") (pintype "passive"))
      (node (ref "JDC1") (pin "1") (pinfunction "T_1") (pintype "passive"))
    )
    (net (code "43") (name "Net-(DIO1-K)") (class "Default")
      (node (ref "C5") (pin "1") (pinfunction "1_1") (pintype "passive"))
      (node (ref "DIO1") (pin "2") (pinfunction "K_2") (pintype "passive"))
      (node (ref "IC2") (pin "1") (pinfunction "I_1") (pintype "power_in"))
    )
    (net (code "44") (name "Net-(DIO2-A)") (class "Default")
      (node (ref "DIO2") (pin "1") (pinfunction "A_1") (pintype "passive"))
      (node (ref "USB1") (pin "1") (pinfunction "VCC_1") (pintype "passive"))
    )
    (net (code "45") (name "Net-(DIO3-A)") (class "Default")
      (node (ref "C14") (pin "2") (pinfunction "2_2") (pintype "passive"))
      (node (ref "DIO3") (pin "1") (pinfunction "A_1") (pintype "passive"))
      (node (ref "Q1") (pin "2") (pinfunction "C_2") (pintype "passive"))
      (node (ref "SP1") (pin "2") (pinfunction "2_2") (pintype "passive"))
    )
    (net (code "46") (name "Net-(DIO4-A)") (class "Default")
      (node (ref "C15") (pin "2") (pinfunction "2_2") (pintype "passive"))
      (node (ref "DIO4") (pin "1") (pinfunction "A_1") (pintype "passive"))
      (node (ref "Q2") (pin "2") (pinfunction "C_2") (pintype "passive"))
      (node (ref "RL1") (pin "4") (pinfunction "4_4") (pintype "passive"))
    )
    (net (code "47") (name "Net-(DS1-V1)") (class "Default")
      (node (ref "DS1") (pin "12") (pinfunction "V1_12") (pintype "passive"))
      (node (ref "Q3") (pin "2") (pinfunction "C_2") (pintype "passive"))
    )
    (net (code "48") (name "Net-(DS1-V2)") (class "Default")
      (node (ref "DS1") (pin "9") (pinfunction "V2_9") (pintype "passive"))
      (node (ref "Q4") (pin "2") (pinfunction "C_2") (pintype "passive"))
    )
    (net (code "49") (name "Net-(DS1-V3)") (class "Default")
      (node (ref "DS1") (pin "8") (pinfunction "V3_8") (pintype "passive"))
      (node (ref "Q5") (pin "2") (pinfunction "C_2") (pintype "passive"))
    )
    (net (code "50") (name "Net-(DS1-V4)") (class "Default")
      (node (ref "DS1") (pin "6") (pinfunction "V4_6") (pintype "passive"))
      (node (ref "Q6") (pin "2") (pinfunction "C_2") (pintype "passive"))
    )
    (net (code "51") (name "Net-(DS1-a)") (class "Default")
      (node (ref "DS1") (pin "11") (pinfunction "a_11") (pintype "passive"))
      (node (ref "R19") (pin "8") (pinfunction "8_8") (pintype "passive"))
    )
    (net (code "52") (name "Net-(DS1-b)") (class "Default")
      (node (ref "DS1") (pin "7") (pinfunction "b_7") (pintype "passive"))
      (node (ref "R19") (pin "7") (pinfunction "7_7") (pintype "passive"))
    )
    (net (code "53") (name "Net-(DS1-c)") (class "Default")
      (node (ref "DS1") (pin "4") (pinfunction "c_4") (pintype "passive"))
      (node (ref "R19") (pin "6") (pinfunction "6_6") (pintype "passive"))
    )
    (net (code "54") (name "Net-(DS1-d)") (class "Default")
      (node (ref "DS1") (pin "2") (pinfunction "d_2") (pintype "passive"))
      (node (ref "R19") (pin "5") (pinfunction "5_5") (pintype "passive"))
    )
    (net (code "55") (name "Net-(DS1-e)") (class "Default")
      (node (ref "DS1") (pin "1") (pinfunction "e_1") (pintype "passive"))
      (node (ref "R20") (pin "8") (pinfunction "8_8") (pintype "passive"))
    )
    (net (code "56") (name "Net-(DS1-f)") (class "Default")
      (node (ref "DS1") (pin "10") (pinfunction "f_10") (pintype "passive"))
      (node (ref "R20") (pin "7") (pinfunction "7_7") (pintype "passive"))
    )
    (net (code "57") (name "Net-(DS1-g)") (class "Default")
      (node (ref "DS1") (pin "5") (pinfunction "g_5") (pintype "passive"))
      (node (ref "R20") (pin "6") (pinfunction "6_6") (pintype "passive"))
    )
    (net (code "58") (name "Net-(DS1-h)") (class "Default")
      (node (ref "DS1") (pin "3") (pinfunction "h_3") (pintype "passive"))
      (node (ref "R20") (pin "5") (pinfunction "5_5") (pintype "passive"))
    )
    (net (code "59") (name "Net-(HD1-Pad1)") (class "Default")
      (node (ref "HD1") (pin "1") (pinfunction "1_1") (pintype "passive"))
      (node (ref "RL1") (pin "3") (pinfunction "3_3") (pintype "passive"))
    )
    (net (code "60") (name "Net-(HD1-Pad2)") (class "Default")
      (node (ref "HD1") (pin "2") (pinfunction "2_2") (pintype "passive"))
      (node (ref "RL1") (pin "1") (pinfunction "1_1") (pintype "passive"))
    )
    (net (code "61") (name "Net-(HD1-Pad3)") (class "Default")
      (node (ref "HD1") (pin "3") (pinfunction "3_3") (pintype "passive"))
      (node (ref "RL1") (pin "2") (pinfunction "2_2") (pintype "passive"))
    )
    (net (code "62") (name "Net-(IC3-XTAL1)") (class "Default")
      (node (ref "C18") (pin "1") (pinfunction "1_1") (pintype "passive"))
      (node (ref "IC3") (pin "18") (pinfunction "XTAL1_18") (pintype "passive"))
      (node (ref "X3") (pin "1") (pinfunction "1_1") (pintype "passive"))
    )
    (net (code "63") (name "Net-(IC3-XTAL2)") (class "Default")
      (node (ref "C19") (pin "1") (pinfunction "1_1") (pintype "passive"))
      (node (ref "IC3") (pin "19") (pinfunction "XTAL2_19") (pintype "passive"))
      (node (ref "X3") (pin "2") (pinfunction "2_2") (pintype "passive"))
    )
    (net (code "64") (name "Net-(LCD1-VEE)") (class "Default")
      (node (ref "LCD1") (pin "3") (pinfunction "VEE_3") (pintype "passive"))
      (node (ref "VR3") (pin "2") (pinfunction "2_2") (pintype "passive"))
    )
    (net (code "65") (name "Net-(LED1-Pad2)") (class "Default")
      (node (ref "LED1") (pin "2") (pinfunction "2_2") (pintype "passive"))
      (node (ref "R2") (pin "1") (pinfunction "1_1") (pintype "passive"))
    )
    (net (code "66") (name "Net-(LED2-Pad2)") (class "Default")
      (node (ref "LED2") (pin "2") (pinfunction "2_2") (pintype "passive"))
      (node (ref "R3") (pin "1") (pinfunction "1_1") (pintype "passive"))
    )
    (net (code "67") (name "Net-(LED4-Pad2)") (class "Default")
      (node (ref "LED4") (pin "2") (pinfunction "2_2") (pintype "passive"))
      (node (ref "R17") (pin "8") (pinfunction "8_8") (pintype "passive"))
    )
    (net (code "68") (name "Net-(LED5-Pad2)") (class "Default")
      (node (ref "LED5") (pin "2") (pinfunction "2_2") (pintype "passive"))
      (node (ref "R17") (pin "7") (pinfunction "7_7") (pintype "passive"))
    )
    (net (code "69") (name "Net-(LED6-Pad2)") (class "Default")
      (node (ref "LED6") (pin "2") (pinfunction "2_2") (pintype "passive"))
      (node (ref "R17") (pin "6") (pinfunction "6_6") (pintype "passive"))
    )
    (net (code "70") (name "Net-(LED7-Pad2)") (class "Default")
      (node (ref "LED7") (pin "2") (pinfunction "2_2") (pintype "passive"))
      (node (ref "R17") (pin "5") (pinfunction "5_5") (pintype "passive"))
    )
    (net (code "71") (name "Net-(LED8-Pad2)") (class "Default")
      (node (ref "LED8") (pin "2") (pinfunction "2_2") (pintype "passive"))
      (node (ref "R18") (pin "8") (pinfunction "8_8") (pintype "passive"))
    )
    (net (code "72") (name "Net-(LED9-Pad2)") (class "Default")
      (node (ref "LED9") (pin "2") (pinfunction "2_2") (pintype "passive"))
      (node (ref "R18") (pin "7") (pinfunction "7_7") (pintype "passive"))
    )
    (net (code "73") (name "Net-(LED10-Pad1)") (class "Default")
      (node (ref "LED10") (pin "1") (pinfunction "1_1") (pintype "passive"))
      (node (ref "LED11") (pin "1") (pinfunction "1_1") (pintype "passive"))
      (node (ref "LED4") (pin "1") (pinfunction "1_1") (pintype "passive"))
      (node (ref "LED5") (pin "1") (pinfunction "1_1") (pintype "passive"))
      (node (ref "LED6") (pin "1") (pinfunction "1_1") (pintype "passive"))
      (node (ref "LED7") (pin "1") (pinfunction "1_1") (pintype "passive"))
      (node (ref "LED8") (pin "1") (pinfunction "1_1") (pintype "passive"))
      (node (ref "LED9") (pin "1") (pinfunction "1_1") (pintype "passive"))
      (node (ref "S7") (pin "1") (pinfunction "1_1") (pintype "passive"))
    )
    (net (code "74") (name "Net-(LED10-Pad2)") (class "Default")
      (node (ref "LED10") (pin "2") (pinfunction "2_2") (pintype "passive"))
      (node (ref "R18") (pin "6") (pinfunction "6_6") (pintype "passive"))
    )
    (net (code "75") (name "Net-(LED11-Pad2)") (class "Default")
      (node (ref "LED11") (pin "2") (pinfunction "2_2") (pintype "passive"))
      (node (ref "R18") (pin "5") (pinfunction "5_5") (pintype "passive"))
    )
    (net (code "76") (name "Net-(Q1-B)") (class "Default")
      (node (ref "Q1") (pin "3") (pinfunction "B_3") (pintype "passive"))
      (node (ref "R5") (pin "1") (pinfunction "1_1") (pintype "passive"))
    )
    (net (code "77") (name "Net-(Q2-B)") (class "Default")
      (node (ref "Q2") (pin "3") (pinfunction "B_3") (pintype "passive"))
      (node (ref "R6") (pin "1") (pinfunction "1_1") (pintype "passive"))
    )
    (net (code "78") (name "Net-(Q3-E)") (class "Default")
      (node (ref "Q3") (pin "1") (pinfunction "E_1") (pintype "passive"))
      (node (ref "Q4") (pin "1") (pinfunction "E_1") (pintype "passive"))
      (node (ref "Q5") (pin "1") (pinfunction "E_1") (pintype "passive"))
      (node (ref "Q6") (pin "1") (pinfunction "E_1") (pintype "passive"))
      (node (ref "S6") (pin "1") (pinfunction "1_1") (pintype "passive"))
    )
    (net (code "79") (name "Net-(R5-Pad2)") (class "Default")
      (node (ref "R5") (pin "2") (pinfunction "2_2") (pintype "passive"))
      (node (ref "S3") (pin "2") (pinfunction "2_2") (pintype "passive"))
    )
    (net (code "80") (name "Net-(R6-Pad2)") (class "Default")
      (node (ref "R6") (pin "2") (pinfunction "2_2") (pintype "passive"))
      (node (ref "S4") (pin "2") (pinfunction "2_2") (pintype "passive"))
    )
    (net (code "81") (name "Net-(R12-Pad1)") (class "Default")
      (node (ref "R12") (pin "1") (pinfunction "1_1") (pintype "passive"))
      (node (ref "R13") (pin "1") (pinfunction "1_1") (pintype "passive"))
      (node (ref "R14") (pin "1") (pinfunction "1_1") (pintype "passive"))
      (node (ref "R15") (pin "1") (pinfunction "1_1") (pintype "passive"))
      (node (ref "R16") (pin "1") (pinfunction "1_1") (pintype "passive"))
      (node (ref "S5") (pin "2") (pinfunction "2_2") (pintype "passive"))
    )
    (net (code "82") (name "Net-(U1-VREF)") (class "Default")
      (node (ref "U1") (pin "14") (pinfunction "VREF_14") (pintype "input"))
      (node (ref "VR2") (pin "2") (pinfunction "2_2") (pintype "passive"))
    )
    (net (code "83") (name "Net-(U5-SQW(Out))") (class "Default")
      (node (ref "LED3") (pin "1") (pinfunction "1_1") (pintype "passive"))
      (node (ref "R4") (pin "1") (pinfunction "1_1") (pintype "passive"))
      (node (ref "U5") (pin "7") (pinfunction "SQW(Out)_7") (pintype "output"))
    )
    (net (code "84") (name "Net-(U5-X1)") (class "Default")
      (node (ref "C11") (pin "1") (pinfunction "1_1") (pintype "passive"))
      (node (ref "U5") (pin "1") (pinfunction "X1_1") (pintype "passive"))
      (node (ref "X1") (pin "2") (pinfunction "2_2") (pintype "passive"))
    )
    (net (code "85") (name "Net-(U5-X2)") (class "Default")
      (node (ref "C12") (pin "1") (pinfunction "1_1") (pintype "passive"))
      (node (ref "U5") (pin "2") (pinfunction "X2_2") (pintype "passive"))
      (node (ref "X1") (pin "1") (pinfunction "1_1") (pintype "passive"))
    )
    (net (code "86") (name "Net-(U6-3V)") (class "Default")
      (node (ref "C13") (pin "2") (pinfunction "2_2") (pintype "passive"))
      (node (ref "U6") (pin "4") (pinfunction "3V_4") (pintype "passive"))
    )
    (net (code "87") (name "Net-(U6-D+)") (class "Default")
      (node (ref "U6") (pin "5") (pinfunction "D+_5") (pintype "passive"))
      (node (ref "USB1") (pin "3") (pinfunction "D+/DM_3") (pintype "passive"))
    )
    (net (code "88") (name "Net-(U6-D-)") (class "Default")
      (node (ref "U6") (pin "6") (pinfunction "D-_6") (pintype "passive"))
      (node (ref "USB1") (pin "2") (pinfunction "D-/DM_2") (pintype "passive"))
    )
    (net (code "89") (name "Net-(U6-RXD)") (class "Default")
      (node (ref "S2") (pin "1") (pinfunction "1_1") (pintype "passive"))
      (node (ref "U6") (pin "3") (pinfunction "RXD_3") (pintype "passive"))
    )
    (net (code "90") (name "Net-(U6-TXD)") (class "Default")
      (node (ref "S1") (pin "1") (pinfunction "1_1") (pintype "passive"))
      (node (ref "U6") (pin "2") (pinfunction "TXD_2") (pintype "passive"))
    )
    (net (code "91") (name "Net-(U6-XI)") (class "Default")
      (node (ref "C16") (pin "1") (pinfunction "1_1") (pintype "passive"))
      (node (ref "U6") (pin "7") (pinfunction "XI_7") (pintype "passive"))
      (node (ref "X2") (pin "1") (pinfunction "1_1") (pintype "passive"))
    )
    (net (code "92") (name "Net-(U6-XO)") (class "Default")
      (node (ref "C17") (pin "1") (pinfunction "1_1") (pintype "passive"))
      (node (ref "U6") (pin "8") (pinfunction "XO_8") (pintype "passive"))
      (node (ref "X2") (pin "2") (pinfunction "2_2") (pintype "passive"))
    )
    (net (code "93") (name "Net-(U8-CH_PD)") (class "Default")
      (node (ref "R8") (pin "2") (pinfunction "2_2") (pintype "passive"))
      (node (ref "U8") (pin "2") (pinfunction "CH_PD_2") (pintype "passive"))
    )
    (net (code "94") (name "Net-(U8-RST)") (class "Default")
      (node (ref "R7") (pin "2") (pinfunction "2_2") (pintype "passive"))
      (node (ref "U8") (pin "3") (pinfunction "RST_3") (pintype "passive"))
    )
    (net (code "95") (name "VCC") (class "Default")
      (node (ref "C1") (pin "1") (pinfunction "VCC_1") (pintype "passive"))
      (node (ref "C10") (pin "1") (pinfunction "1_1") (pintype "passive"))
      (node (ref "C14") (pin "1") (pinfunction "1_1") (pintype "passive"))
      (node (ref "C15") (pin "1") (pinfunction "1_1") (pintype "passive"))
      (node (ref "C20") (pin "1") (pinfunction "1_1") (pintype "passive"))
      (node (ref "C21") (pin "17") (pinfunction "17_17") (pintype "passive"))
      (node (ref "C21") (pin "24") (pinfunction "24_24") (pintype "passive"))
      (node (ref "C6") (pin "1") (pinfunction "1_1") (pintype "passive"))
      (node (ref "C7") (pin "1") (pinfunction "1_1") (pintype "passive"))
      (node (ref "DIO2") (pin "2") (pinfunction "K_2") (pintype "passive"))
      (node (ref "DIO3") (pin "2") (pinfunction "K_2") (pintype "passive"))
      (node (ref "DIO4") (pin "2") (pinfunction "K_2") (pintype "passive"))
      (node (ref "IC1") (pin "8") (pinfunction "VCC_8") (pintype "power_in"))
      (node (ref "IC2") (pin "3") (pinfunction "O_3") (pintype "power_in"))
      (node (ref "IC3") (pin "31") (pinfunction "~{EA}/VPP_31") (pintype "passive"))
      (node (ref "IC3") (pin "40") (pinfunction "VCC_40") (pintype "power_in"))
      (node (ref "IDE_1") (pin "2") (pinfunction "VCC_2") (pintype "power_in"))
      (node (ref "IR1") (pin "3") (pinfunction "VCC_3") (pintype "passive"))
      (node (ref "LCD1") (pin "15") (pinfunction "A_15") (pintype "passive"))
      (node (ref "LCD1") (pin "2") (pinfunction "VDD_2") (pintype "passive"))
      (node (ref "LED2") (pin "1") (pinfunction "1_1") (pintype "passive"))
      (node (ref "R1") (pin "1") (pinfunction "1_1") (pintype "passive"))
      (node (ref "R10") (pin "1") (pinfunction "1_1") (pintype "passive"))
      (node (ref "R4") (pin "2") (pinfunction "2_2") (pintype "passive"))
      (node (ref "R9") (pin "1") (pinfunction "1_1") (pintype "passive"))
      (node (ref "RL1") (pin "5") (pinfunction "5_5") (pintype "passive"))
      (node (ref "RPB1") (pin "1") (pinfunction "1_1") (pintype "passive"))
      (node (ref "S5") (pin "1") (pinfunction "1_1") (pintype "passive"))
      (node (ref "S6") (pin "2") (pinfunction "2_2") (pintype "passive"))
      (node (ref "S7") (pin "2") (pinfunction "2_2") (pintype "passive"))
      (node (ref "SP1") (pin "1") (pinfunction "1_1") (pintype "passive"))
      (node (ref "SW1") (pin "1") (pinfunction "1_1") (pintype "passive"))
      (node (ref "U1") (pin "16") (pinfunction "VDD_16") (pintype "power_in"))
      (node (ref "U2") (pin "3") (pinfunction "VCC_3") (pintype "passive"))
      (node (ref "U3") (pin "1") (pinfunction "+Vs_1") (pintype "passive"))
      (node (ref "U4") (pin "3") (pinfunction "IN_3") (pintype "power_in"))
      (node (ref "U5") (pin "8") (pinfunction "Vcc_8") (pintype "power_in"))
      (node (ref "U6") (pin "16") (pinfunction "VCC_16") (pintype "passive"))
      (node (ref "U7") (pin "5") (pinfunction "VCC_5") (pintype "power_in"))
      (node (ref "VR1") (pin "1") (pinfunction "1_1") (pintype "passive"))
      (node (ref "VR2") (pin "1") (pinfunction "1_1") (pintype "passive"))
      (node (ref "VR3") (pin "1") (pinfunction "1_1") (pintype "passive"))
    )
    (net (code "96") (name "unconnected-(C1-NC-Pad3)") (class "Default")
      (node (ref "C1") (pin "3") (pinfunction "NC_3") (pintype "passive"))
    )
    (net (code "97") (name "unconnected-(IC3-ALE{slash}~{PROG}-Pad30)") (class "Default")
      (node (ref "IC3") (pin "30") (pinfunction "ALE/~{PROG}_30") (pintype "passive"))
    )
    (net (code "98") (name "unconnected-(IC3-~{PSEN}-Pad29)") (class "Default")
      (node (ref "IC3") (pin "29") (pinfunction "~{PSEN}_29") (pintype "passive"))
    )
    (net (code "99") (name "unconnected-(IDE_1-XTAL1-Pad3)") (class "Default")
      (node (ref "IDE_1") (pin "3") (pinfunction "XTAL1_3") (pintype "passive"))
    )
    (net (code "100") (name "unconnected-(LCD1-D0-Pad7)") (class "Default")
      (node (ref "LCD1") (pin "7") (pinfunction "D0_7") (pintype "passive"))
    )
    (net (code "101") (name "unconnected-(LCD1-D1-Pad8)") (class "Default")
      (node (ref "LCD1") (pin "8") (pinfunction "D1_8") (pintype "passive"))
    )
    (net (code "102") (name "unconnected-(LCD1-D2-Pad9)") (class "Default")
      (node (ref "LCD1") (pin "9") (pinfunction "D2_9") (pintype "passive"))
    )
    (net (code "103") (name "unconnected-(LCD1-D3-Pad10)") (class "Default")
      (node (ref "LCD1") (pin "10") (pinfunction "D3_10") (pintype "passive"))
    )
    (net (code "104") (name "unconnected-(U1-OSC-Pad11)") (class "Default")
      (node (ref "U1") (pin "11") (pinfunction "OSC_11") (pintype "bidirectional"))
    )
    (net (code "105") (name "unconnected-(U6-CTR#-Pad9)") (class "Default")
      (node (ref "U6") (pin "9") (pinfunction "CTR#_9") (pintype "passive"))
    )
    (net (code "106") (name "unconnected-(U6-DCD#-Pad12)") (class "Default")
      (node (ref "U6") (pin "12") (pinfunction "DCD#_12") (pintype "passive"))
    )
    (net (code "107") (name "unconnected-(U6-DSR#-Pad10)") (class "Default")
      (node (ref "U6") (pin "10") (pinfunction "DSR#_10") (pintype "passive"))
    )
    (net (code "108") (name "unconnected-(U6-DTR#-Pad13)") (class "Default")
      (node (ref "U6") (pin "13") (pinfunction "DTR#_13") (pintype "passive"))
    )
    (net (code "109") (name "unconnected-(U6-RI#-Pad11)") (class "Default")
      (node (ref "U6") (pin "11") (pinfunction "RI#_11") (pintype "passive"))
    )
    (net (code "110") (name "unconnected-(U6-RS232-Pad15)") (class "Default")
      (node (ref "U6") (pin "15") (pinfunction "RS232_15") (pintype "passive"))
    )
    (net (code "111") (name "unconnected-(U6-RTS#-Pad14)") (class "Default")
      (node (ref "U6") (pin "14") (pinfunction "RTS#_14") (pintype "passive"))
    )
    (net (code "112") (name "unconnected-(U7-EN-Pad6)") (class "Default")
      (node (ref "U7") (pin "6") (pinfunction "EN_6") (pintype "input"))
    )
    (net (code "113") (name "unconnected-(U7-STATE-Pad1)") (class "Default")
      (node (ref "U7") (pin "1") (pinfunction "STATE_1") (pintype "output"))
    )
    (net (code "114") (name "unconnected-(U8-GPIO0-Pad6)") (class "Default")
      (node (ref "U8") (pin "6") (pinfunction "GPIO0_6") (pintype "passive"))
    )
    (net (code "115") (name "unconnected-(U8-GPIO2-Pad7)") (class "Default")
      (node (ref "U8") (pin "7") (pinfunction "GPIO2_7") (pintype "passive"))
    )
    (net (code "116") (name "unconnected-(USB1-ID-Pad4)") (class "Default")
      (node (ref "USB1") (pin "4") (pinfunction "ID_4") (pintype "passive"))
    )
  )
)
